# placa_motor_v1.net
KiCad netlist of a schematic drawn in EAGLE
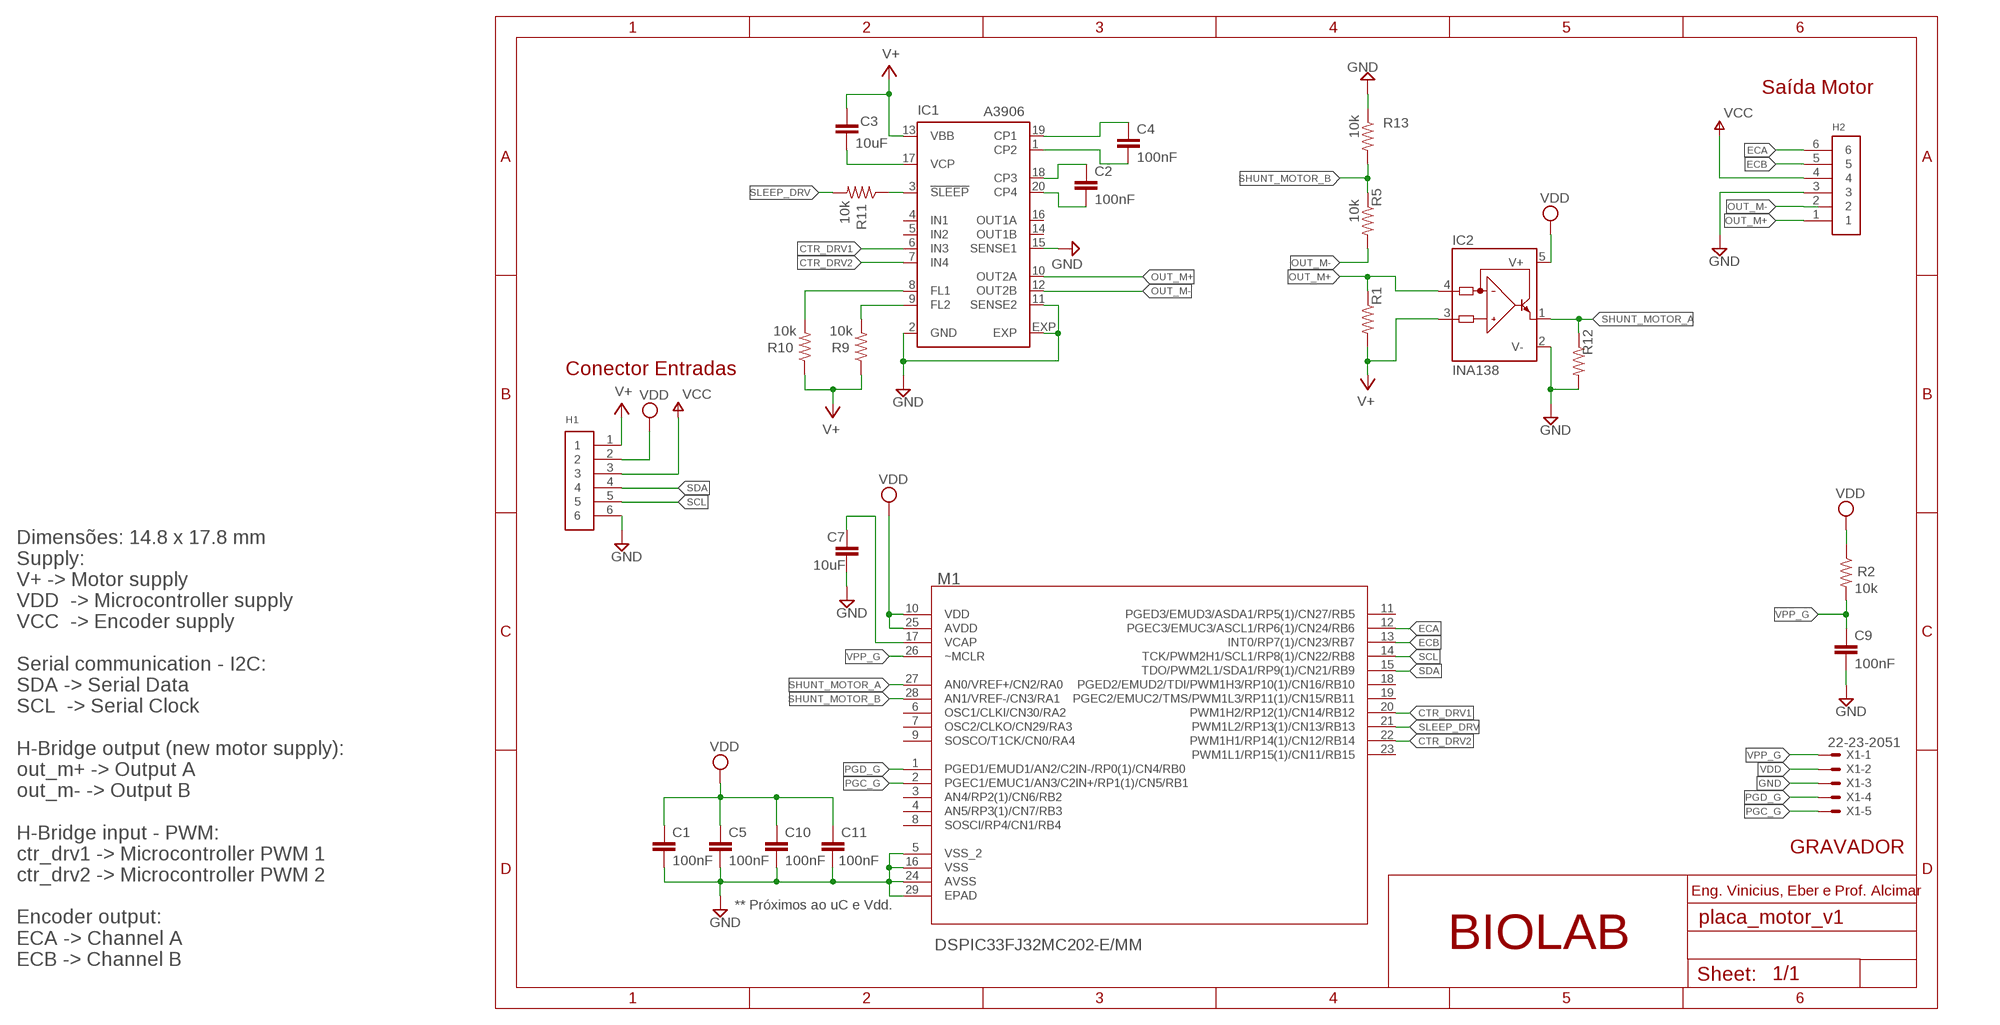
[diagram p0: schematic, sheet 1]

(export (version "E")
  (design (tool "Eeschema 10.0.6"))
  (components
    (comp (ref "C1")
      (value "100nF")
      (footprint "eagle-import:RESC0805_M")
      (libsource (lib "eagle-import") (part "CAPACITOR_0805_M"))
    )
    (comp (ref "C2")
      (value "100nF")
      (footprint "eagle-import:RESC0805_M")
      (libsource (lib "eagle-import") (part "CAPACITOR_0805_M"))
    )
    (comp (ref "C3")
      (value "10uF")
      (footprint "eagle-import:RESC0805_M")
      (libsource (lib "eagle-import") (part "CAPACITOR_0805_M"))
    )
    (comp (ref "C4")
      (value "100nF")
      (footprint "eagle-import:RESC0805_M")
      (libsource (lib "eagle-import") (part "CAPACITOR_0805_M"))
    )
    (comp (ref "C5")
      (value "100nF")
      (footprint "eagle-import:RESC0805_M")
      (libsource (lib "eagle-import") (part "CAPACITOR_0805_M"))
    )
    (comp (ref "C7")
      (value "10uF")
      (footprint "eagle-import:RESC0805_M")
      (libsource (lib "eagle-import") (part "CAPACITOR_0805_M"))
    )
    (comp (ref "C9")
      (value "100nF")
      (footprint "eagle-import:RESC0805_M")
      (libsource (lib "eagle-import") (part "CAPACITOR_0805_M"))
    )
    (comp (ref "C10")
      (value "100nF")
      (footprint "eagle-import:RESC0805_M")
      (libsource (lib "eagle-import") (part "CAPACITOR_0805_M"))
    )
    (comp (ref "C11")
      (value "100nF")
      (footprint "eagle-import:RESC0805_M")
      (libsource (lib "eagle-import") (part "CAPACITOR_0805_M"))
    )
    (comp (ref "H1")
      (value "61300611121")
      (footprint "eagle-import:61300611121")
      (fields
        (field (name "DIGI_KEY_PART_NUMBER") "732-5319-ND")
        (field (name "MANUFACTURER") "Wurth Electronics Inc.")
        (field (name "CREATED_BY") "PCBLayout.com")
      )
      (libsource (lib "eagle-import") (part "61300611121"))
    )
    (comp (ref "H2")
      (value "61300611121")
      (footprint "eagle-import:61300611121")
      (fields
        (field (name "DIGI_KEY_PART_NUMBER") "732-5319-ND")
        (field (name "MANUFACTURER") "Wurth Electronics Inc.")
        (field (name "CREATED_BY") "PCBLayout.com")
      )
      (libsource (lib "eagle-import") (part "61300611121"))
    )
    (comp (ref "IC1")
      (value "A3906")
      (footprint "eagle-import:QFN20")
      (libsource (lib "eagle-import") (part "A3906"))
    )
    (comp (ref "IC2")
      (value "INA138")
      (footprint "eagle-import:SOT23-5")
      (fields (field (name "MF") "TEXAS INSTRUMENTS") (field (name "MPN") "INA138NA/250"))
      (libsource (lib "eagle-import") (part "INA138"))
    )
    (comp (ref "M1")
      (value "DSPIC33FJ32MC202-E/MM")
      (footprint "eagle-import:QFN65P600X600X100-29N")
      (fields
        (field (name "DIGI-KEY_PART_NUMBER") "DSPIC33FJ32MC202-E/MM-ND")
        (field (name "MF") "Microchip")
      )
      (libsource (lib "eagle-import") (part "DSPIC33FJ32MC202-E/MM"))
    )
    (comp (ref "R1")
      (value "R-US_R0805")
      (footprint "eagle-import:R0805")
      (libsource (lib "eagle-import") (part "R-US_R0805"))
    )
    (comp (ref "R2")
      (value "10k")
      (footprint "eagle-import:R0805")
      (libsource (lib "eagle-import") (part "R-US_R0805"))
    )
    (comp (ref "R5")
      (value "10k")
      (footprint "eagle-import:R0805")
      (libsource (lib "eagle-import") (part "R-US_R0805"))
    )
    (comp (ref "R9")
      (value "10k")
      (footprint "eagle-import:R0805")
      (libsource (lib "eagle-import") (part "R-US_R0805"))
    )
    (comp (ref "R10")
      (value "10k")
      (footprint "eagle-import:R0805")
      (libsource (lib "eagle-import") (part "R-US_R0805"))
    )
    (comp (ref "R11")
      (value "10k")
      (footprint "eagle-import:R0805")
      (libsource (lib "eagle-import") (part "R-US_R0805"))
    )
    (comp (ref "R12")
      (value "R-US_R0805")
      (footprint "eagle-import:R0805")
      (libsource (lib "eagle-import") (part "R-US_R0805"))
    )
    (comp (ref "R13")
      (value "10k")
      (footprint "eagle-import:R0805")
      (libsource (lib "eagle-import") (part "R-US_R0805"))
    )
    (comp (ref "X1")
      (value "22-23-2051")
      (footprint "eagle-import:22-23-2051")
      (fields (field (name "MF") "MOLEX"))
      (libsource (lib "eagle-import") (part "22-23-2051"))
    )
  )
  (nets
    (net (code "1") (name "CTR_DRV1") (class "Default")
      (node (ref "IC1") (pin "6") (pinfunction "IN3_6") (pintype "input"))
      (node (ref "M1") (pin "20") (pinfunction "PWM1H2/RP12(1)/CN14/RB12_20") (pintype "bidirectional"))
    )
    (net (code "2") (name "CTR_DRV2") (class "Default")
      (node (ref "IC1") (pin "7") (pinfunction "IN4_7") (pintype "input"))
      (node (ref "M1") (pin "22") (pinfunction "PWM1H1/RP14(1)/CN12/RB14_22") (pintype "bidirectional"))
    )
    (net (code "3") (name "ECA") (class "Default")
      (node (ref "H2") (pin "6") (pinfunction "6_6") (pintype "passive"))
      (node (ref "M1") (pin "12") (pinfunction "PGEC3/EMUC3/ASCL1/RP6(1)/CN24/RB6_12") (pintype "bidirectional"))
    )
    (net (code "4") (name "ECB") (class "Default")
      (node (ref "H2") (pin "5") (pinfunction "5_5") (pintype "passive"))
      (node (ref "M1") (pin "13") (pinfunction "INT0/RP7(1)/CN23/RB7_13") (pintype "bidirectional"))
    )
    (net (code "5") (name "GND") (class "Default")
      (node (ref "C1") (pin "2") (pinfunction "2_2") (pintype "passive"))
      (node (ref "C10") (pin "2") (pinfunction "2_2") (pintype "passive"))
      (node (ref "C11") (pin "2") (pinfunction "2_2") (pintype "passive"))
      (node (ref "C5") (pin "2") (pinfunction "2_2") (pintype "passive"))
      (node (ref "C7") (pin "2") (pinfunction "2_2") (pintype "passive"))
      (node (ref "C9") (pin "2") (pinfunction "2_2") (pintype "passive"))
      (node (ref "H1") (pin "6") (pinfunction "6_6") (pintype "passive"))
      (node (ref "H2") (pin "3") (pinfunction "3_3") (pintype "passive"))
      (node (ref "IC1") (pin "11") (pinfunction "SENSE2_11") (pintype "input"))
      (node (ref "IC1") (pin "15") (pinfunction "SENSE1_15") (pintype "input"))
      (node (ref "IC1") (pin "2") (pinfunction "GND_2") (pintype "power_in"))
      (node (ref "IC1") (pin "EXP") (pinfunction "EXP_EXP") (pintype "passive"))
      (node (ref "IC2") (pin "2") (pinfunction "V-_2") (pintype "power_in"))
      (node (ref "M1") (pin "16") (pinfunction "VSS_16") (pintype "power_in"))
      (node (ref "M1") (pin "24") (pinfunction "AVSS_24") (pintype "power_in"))
      (node (ref "M1") (pin "29") (pinfunction "EPAD_29") (pintype "passive"))
      (node (ref "M1") (pin "5") (pinfunction "VSS_2_5") (pintype "power_in"))
      (node (ref "R12") (pin "2") (pinfunction "2_2") (pintype "passive"))
      (node (ref "R13") (pin "1") (pinfunction "1_1") (pintype "passive"))
      (node (ref "X1") (pin "3") (pinfunction "S_3") (pintype "passive"))
    )
    (net (code "6") (name "Net-(IC1-CP1)") (class "Default")
      (node (ref "C4") (pin "1") (pinfunction "1_1") (pintype "passive"))
      (node (ref "IC1") (pin "19") (pinfunction "CP1_19") (pintype "passive"))
    )
    (net (code "7") (name "Net-(IC1-CP2)") (class "Default")
      (node (ref "C4") (pin "2") (pinfunction "2_2") (pintype "passive"))
      (node (ref "IC1") (pin "1") (pinfunction "CP2_1") (pintype "passive"))
    )
    (net (code "8") (name "Net-(IC1-CP3)") (class "Default")
      (node (ref "C2") (pin "1") (pinfunction "1_1") (pintype "passive"))
      (node (ref "IC1") (pin "18") (pinfunction "CP3_18") (pintype "passive"))
    )
    (net (code "9") (name "Net-(IC1-CP4)") (class "Default")
      (node (ref "C2") (pin "2") (pinfunction "2_2") (pintype "passive"))
      (node (ref "IC1") (pin "20") (pinfunction "CP4_20") (pintype "passive"))
    )
    (net (code "10") (name "Net-(IC1-FL1)") (class "Default")
      (node (ref "IC1") (pin "8") (pinfunction "FL1_8") (pintype "input"))
      (node (ref "R10") (pin "2") (pinfunction "2_2") (pintype "passive"))
    )
    (net (code "11") (name "Net-(IC1-FL2)") (class "Default")
      (node (ref "IC1") (pin "9") (pinfunction "FL2_9") (pintype "input"))
      (node (ref "R9") (pin "2") (pinfunction "2_2") (pintype "passive"))
    )
    (net (code "12") (name "Net-(IC1-VCP)") (class "Default")
      (node (ref "C3") (pin "2") (pinfunction "2_2") (pintype "passive"))
      (node (ref "IC1") (pin "17") (pinfunction "VCP_17") (pintype "passive"))
    )
    (net (code "13") (name "Net-(IC1-~{SLEEP})") (class "Default")
      (node (ref "IC1") (pin "3") (pinfunction "~{SLEEP}_3") (pintype "input"))
      (node (ref "R11") (pin "1") (pinfunction "1_1") (pintype "passive"))
    )
    (net (code "14") (name "Net-(M1-VCAP)") (class "Default")
      (node (ref "C7") (pin "1") (pinfunction "1_1") (pintype "passive"))
      (node (ref "M1") (pin "17") (pinfunction "VCAP_17") (pintype "power_in"))
    )
    (net (code "15") (name "OUT_M+") (class "Default")
      (node (ref "H2") (pin "1") (pinfunction "1_1") (pintype "passive"))
      (node (ref "IC1") (pin "10") (pinfunction "OUT2A_10") (pintype "output"))
      (node (ref "IC2") (pin "4") (pinfunction "IN-_4") (pintype "input"))
      (node (ref "R1") (pin "1") (pinfunction "1_1") (pintype "passive"))
    )
    (net (code "16") (name "OUT_M-") (class "Default")
      (node (ref "H2") (pin "2") (pinfunction "2_2") (pintype "passive"))
      (node (ref "IC1") (pin "12") (pinfunction "OUT2B_12") (pintype "output"))
      (node (ref "R5") (pin "2") (pinfunction "2_2") (pintype "passive"))
    )
    (net (code "17") (name "PGC_G") (class "Default")
      (node (ref "M1") (pin "2") (pinfunction "PGEC1/EMUC1/AN3/C2IN+/RP1(1)/CN5/RB1_2") (pintype "bidirectional"))
      (node (ref "X1") (pin "5") (pinfunction "S_5") (pintype "passive"))
    )
    (net (code "18") (name "PGD_G") (class "Default")
      (node (ref "M1") (pin "1") (pinfunction "PGED1/EMUD1/AN2/C2IN-/RP0(1)/CN4/RB0_1") (pintype "bidirectional"))
      (node (ref "X1") (pin "4") (pinfunction "S_4") (pintype "passive"))
    )
    (net (code "19") (name "SCL") (class "Default")
      (node (ref "H1") (pin "5") (pinfunction "5_5") (pintype "passive"))
      (node (ref "M1") (pin "14") (pinfunction "TCK/PWM2H1/SCL1/RP8(1)/CN22/RB8_14") (pintype "bidirectional"))
    )
    (net (code "20") (name "SDA") (class "Default")
      (node (ref "H1") (pin "4") (pinfunction "4_4") (pintype "passive"))
      (node (ref "M1") (pin "15") (pinfunction "TDO/PWM2L1/SDA1/RP9(1)/CN21/RB9_15") (pintype "bidirectional"))
    )
    (net (code "21") (name "SHUNT_MOTOR_A") (class "Default")
      (node (ref "IC2") (pin "1") (pinfunction "OUT_1") (pintype "output"))
      (node (ref "M1") (pin "27") (pinfunction "AN0/VREF+/CN2/RA0_27") (pintype "bidirectional"))
      (node (ref "R12") (pin "1") (pinfunction "1_1") (pintype "passive"))
    )
    (net (code "22") (name "SHUNT_MOTOR_B") (class "Default")
      (node (ref "M1") (pin "28") (pinfunction "AN1/VREF-/CN3/RA1_28") (pintype "bidirectional"))
      (node (ref "R13") (pin "2") (pinfunction "2_2") (pintype "passive"))
      (node (ref "R5") (pin "1") (pinfunction "1_1") (pintype "passive"))
    )
    (net (code "23") (name "SLEEP_DRV") (class "Default")
      (node (ref "M1") (pin "21") (pinfunction "PWM1L2/RP13(1)/CN13/RB13_21") (pintype "bidirectional"))
      (node (ref "R11") (pin "2") (pinfunction "2_2") (pintype "passive"))
    )
    (net (code "24") (name "V+") (class "Default")
      (node (ref "C3") (pin "1") (pinfunction "1_1") (pintype "passive"))
      (node (ref "H1") (pin "1") (pinfunction "1_1") (pintype "passive"))
      (node (ref "H1") (pin "3") (pinfunction "3_3") (pintype "passive"))
      (node (ref "H2") (pin "4") (pinfunction "4_4") (pintype "passive"))
      (node (ref "IC1") (pin "13") (pinfunction "VBB_13") (pintype "power_in"))
      (node (ref "IC2") (pin "3") (pinfunction "IN+_3") (pintype "input"))
      (node (ref "R1") (pin "2") (pinfunction "2_2") (pintype "passive"))
      (node (ref "R10") (pin "1") (pinfunction "1_1") (pintype "passive"))
      (node (ref "R9") (pin "1") (pinfunction "1_1") (pintype "passive"))
    )
    (net (code "25") (name "VDD") (class "Default")
      (node (ref "C1") (pin "1") (pinfunction "1_1") (pintype "passive"))
      (node (ref "C10") (pin "1") (pinfunction "1_1") (pintype "passive"))
      (node (ref "C11") (pin "1") (pinfunction "1_1") (pintype "passive"))
      (node (ref "C5") (pin "1") (pinfunction "1_1") (pintype "passive"))
      (node (ref "H1") (pin "2") (pinfunction "2_2") (pintype "passive"))
      (node (ref "IC2") (pin "5") (pinfunction "V+_5") (pintype "power_in"))
      (node (ref "M1") (pin "10") (pinfunction "VDD_10") (pintype "power_in"))
      (node (ref "M1") (pin "25") (pinfunction "AVDD_25") (pintype "power_in"))
      (node (ref "R2") (pin "1") (pinfunction "1_1") (pintype "passive"))
      (node (ref "X1") (pin "2") (pinfunction "S_2") (pintype "passive"))
    )
    (net (code "26") (name "VPP_G") (class "Default")
      (node (ref "C9") (pin "1") (pinfunction "1_1") (pintype "passive"))
      (node (ref "M1") (pin "26") (pinfunction "~{MCLR}_26") (pintype "input"))
      (node (ref "R2") (pin "2") (pinfunction "2_2") (pintype "passive"))
      (node (ref "X1") (pin "1") (pinfunction "S_1") (pintype "passive"))
    )
    (net (code "27") (name "unconnected-(IC1-IN1-Pad4)") (class "Default")
      (node (ref "IC1") (pin "4") (pinfunction "IN1_4") (pintype "input"))
    )
    (net (code "28") (name "unconnected-(IC1-IN2-Pad5)") (class "Default")
      (node (ref "IC1") (pin "5") (pinfunction "IN2_5") (pintype "input"))
    )
    (net (code "29") (name "unconnected-(IC1-OUT1A-Pad16)") (class "Default")
      (node (ref "IC1") (pin "16") (pinfunction "OUT1A_16") (pintype "output"))
    )
    (net (code "30") (name "unconnected-(IC1-OUT1B-Pad14)") (class "Default")
      (node (ref "IC1") (pin "14") (pinfunction "OUT1B_14") (pintype "output"))
    )
    (net (code "31") (name "unconnected-(M1-AN4{slash}RP2(1){slash}CN6{slash}RB2-Pad3)") (class "Default")
      (node (ref "M1") (pin "3") (pinfunction "AN4/RP2(1)/CN6/RB2_3") (pintype "bidirectional"))
    )
    (net (code "32") (name "unconnected-(M1-AN5{slash}RP3(1){slash}CN7{slash}RB3-Pad4)") (class "Default")
      (node (ref "M1") (pin "4") (pinfunction "AN5/RP3(1)/CN7/RB3_4") (pintype "bidirectional"))
    )
    (net (code "33") (name "unconnected-(M1-OSC1{slash}CLKI{slash}CN30{slash}RA2-Pad6)") (class "Default")
      (node (ref "M1") (pin "6") (pinfunction "OSC1/CLKI/CN30/RA2_6") (pintype "bidirectional"))
    )
    (net (code "34") (name "unconnected-(M1-OSC2{slash}CLKO{slash}CN29{slash}RA3-Pad7)") (class "Default")
      (node (ref "M1") (pin "7") (pinfunction "OSC2/CLKO/CN29/RA3_7") (pintype "bidirectional"))
    )
    (net (code "35") (name "unconnected-(M1-PGEC2{slash}EMUC2{slash}TMS{slash}PWM1L3{slash}RP11(1){slash}CN15{slash}RB11-Pad19)") (class "Default")
      (node (ref "M1") (pin "19") (pinfunction "PGEC2/EMUC2/TMS/PWM1L3/RP11(1)/CN15/RB11_19") (pintype "bidirectional"))
    )
    (net (code "36") (name "unconnected-(M1-PGED2{slash}EMUD2{slash}TDI{slash}PWM1H3{slash}RP10(1){slash}CN16{slash}RB10-Pad18)") (class "Default")
      (node (ref "M1") (pin "18") (pinfunction "PGED2/EMUD2/TDI/PWM1H3/RP10(1)/CN16/RB10_18") (pintype "bidirectional"))
    )
    (net (code "37") (name "unconnected-(M1-PGED3{slash}EMUD3{slash}ASDA1{slash}RP5(1){slash}CN27{slash}RB5-Pad11)") (class "Default")
      (node (ref "M1") (pin "11") (pinfunction "PGED3/EMUD3/ASDA1/RP5(1)/CN27/RB5_11") (pintype "bidirectional"))
    )
    (net (code "38") (name "unconnected-(M1-PWM1L1{slash}RP15(1){slash}CN11{slash}RB15-Pad23)") (class "Default")
      (node (ref "M1") (pin "23") (pinfunction "PWM1L1/RP15(1)/CN11/RB15_23") (pintype "bidirectional"))
    )
    (net (code "39") (name "unconnected-(M1-SOSCI{slash}RP4{slash}CN1{slash}RB4-Pad8)") (class "Default")
      (node (ref "M1") (pin "8") (pinfunction "SOSCI/RP4/CN1/RB4_8") (pintype "bidirectional"))
    )
    (net (code "40") (name "unconnected-(M1-SOSCO{slash}T1CK{slash}CN0{slash}RA4-Pad9)") (class "Default")
      (node (ref "M1") (pin "9") (pinfunction "SOSCO/T1CK/CN0/RA4_9") (pintype "bidirectional"))
    )
  )
)
